# PWR_DC_DC_EXAR2.net
KiCad netlist of a schematic drawn in Altium Designer
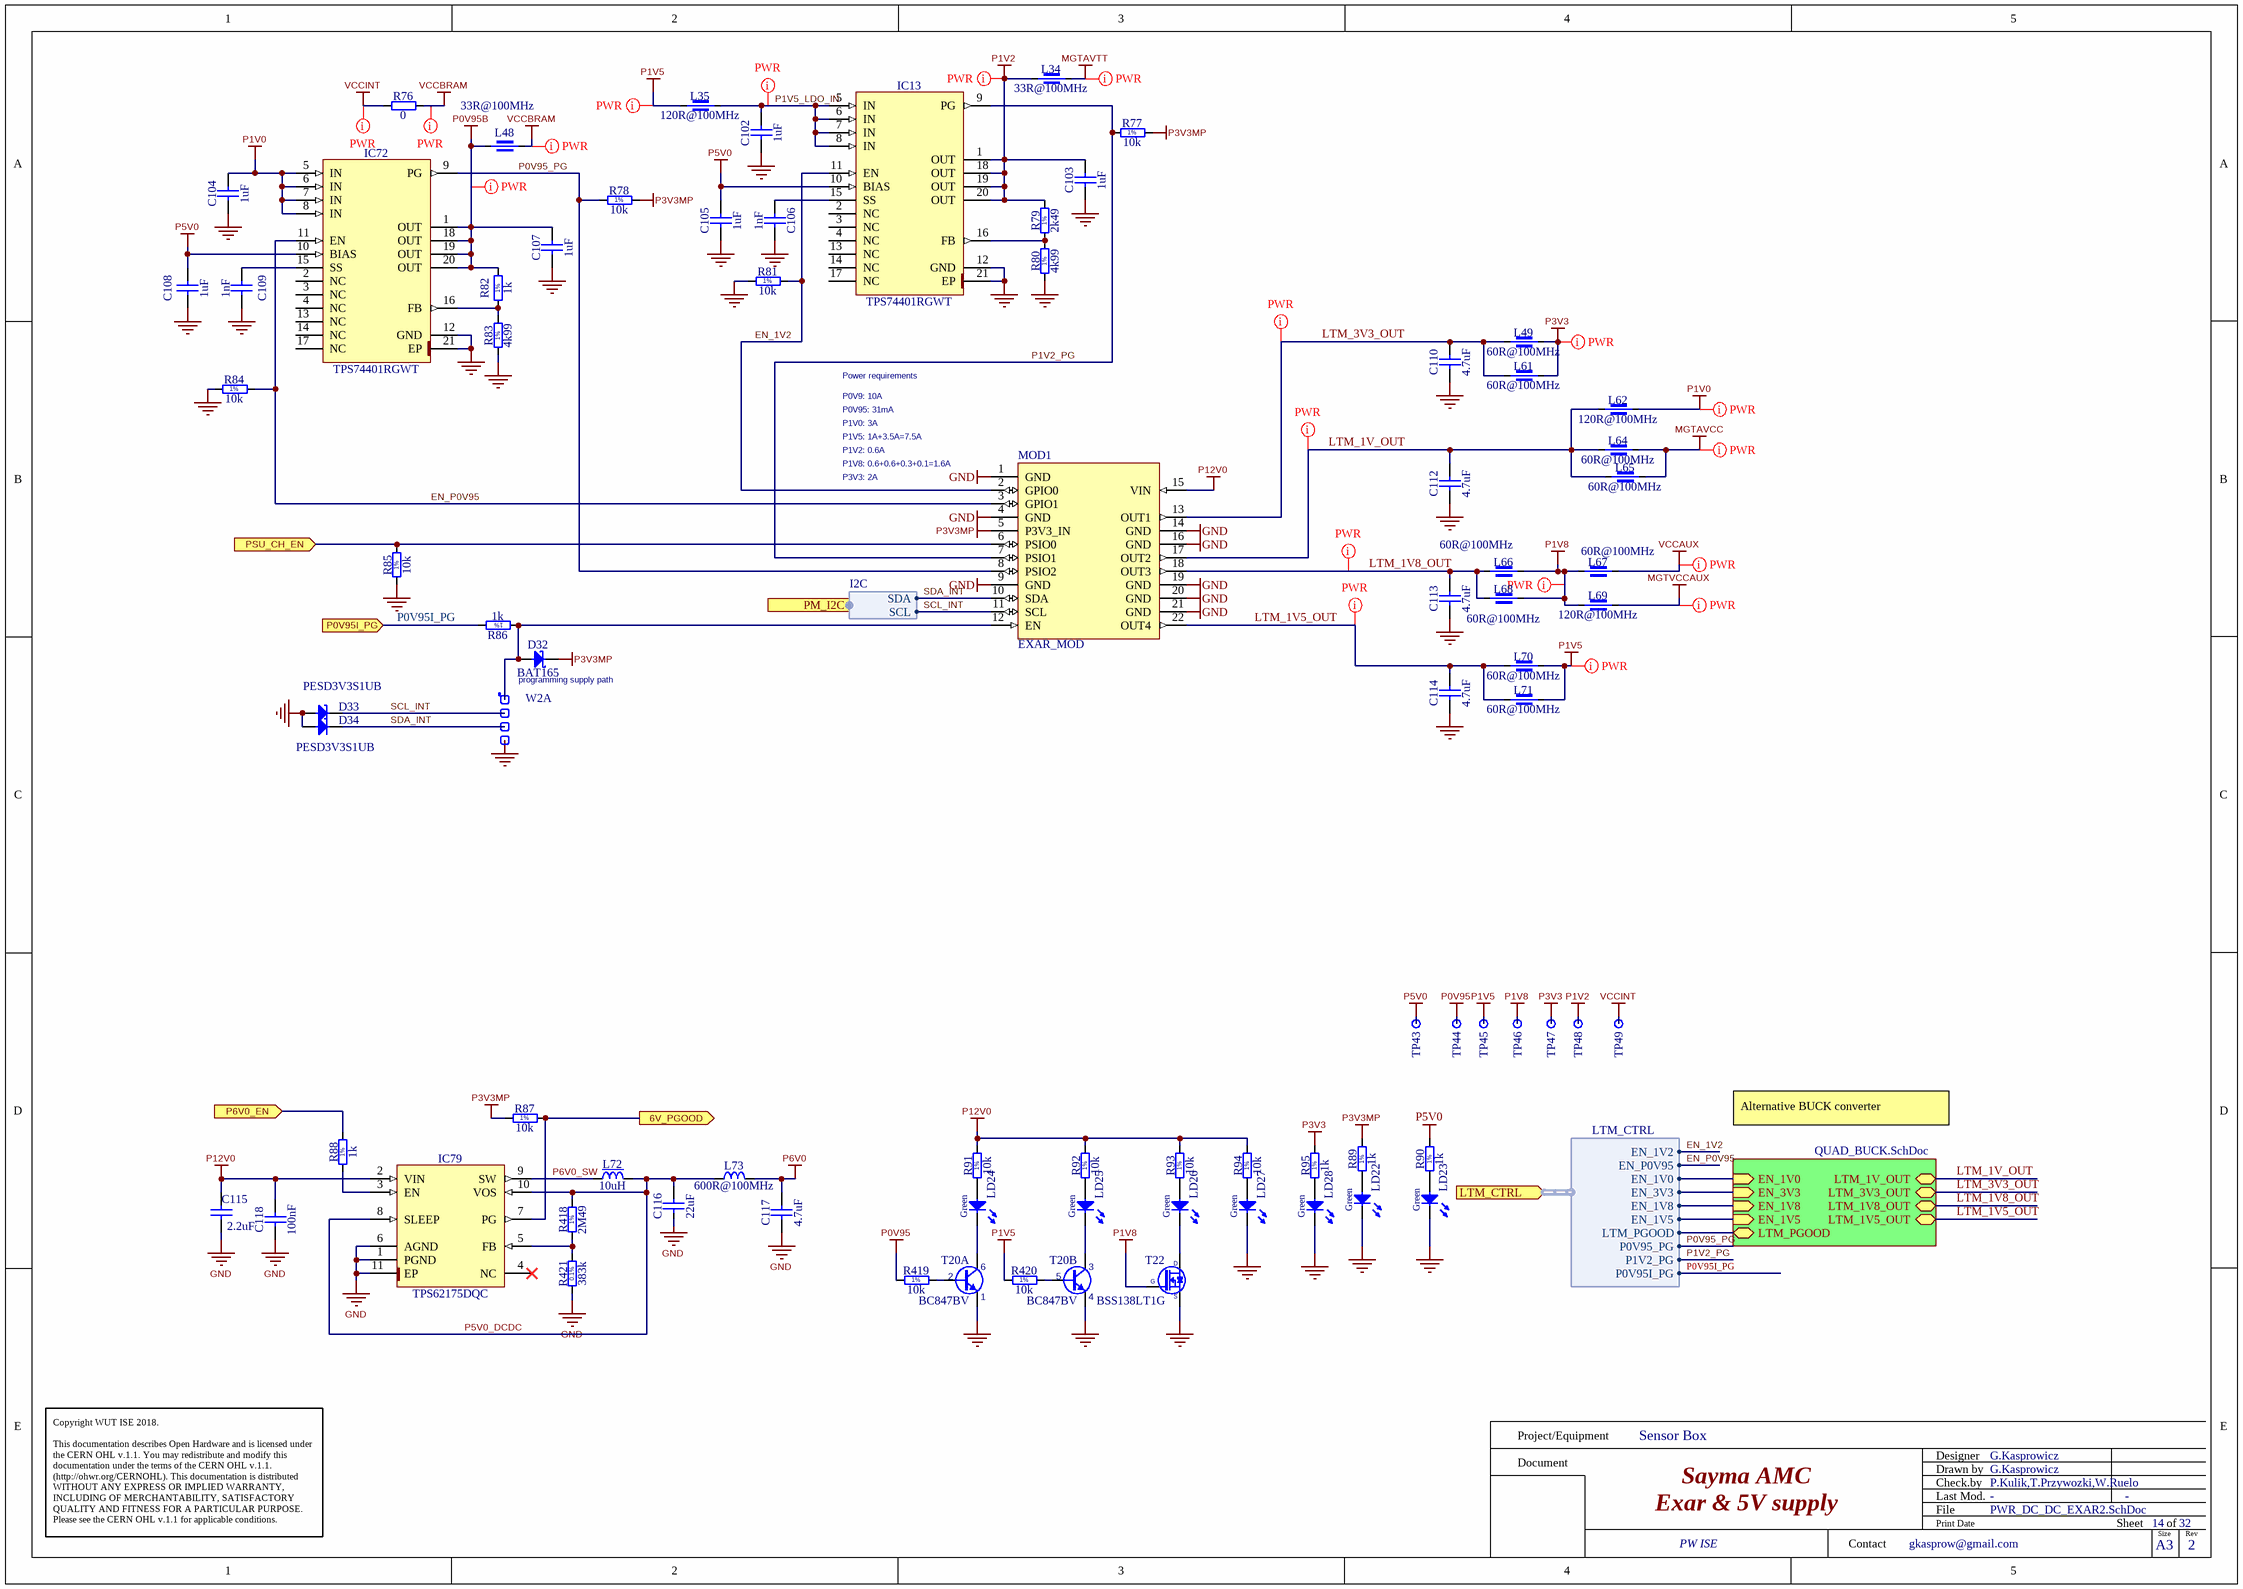
[diagram p0: PWR_DC_DC_EXAR2.SchDoc]

(export (version "E")
  (design (tool "Eeschema 10.0.6"))
  (components
    (comp (ref "C102")
      (value "1uF")
      (footprint "CAPC1005X55N")
      (description "Non-polarised capacitor")
      (fields
        (field (name "MANUFACTURER PART NUMBER") "CC0402_1UF_16V_10%_X5R")
        (field (name "MANUFACTURER") "GENERIC")
        (field (name "AUTHOR") "CERN DEM JLC")
      )
      (libsource (lib "Capacitors") (part "Capacitor - non polarized"))
    )
    (comp (ref "C103")
      (value "1uF")
      (footprint "CAPC1005X55N")
      (description "Non-polarised capacitor")
      (fields
        (field (name "MANUFACTURER PART NUMBER") "CC0402_1UF_16V_10%_X5R")
        (field (name "MANUFACTURER") "GENERIC")
        (field (name "AUTHOR") "CERN DEM JLC")
      )
      (libsource (lib "Capacitors") (part "Capacitor - non polarized"))
    )
    (comp (ref "C104")
      (value "1uF")
      (footprint "CAPC1005X55N")
      (description "Non-polarised capacitor")
      (fields
        (field (name "MANUFACTURER PART NUMBER") "CC0402_1UF_16V_10%_X5R")
        (field (name "MANUFACTURER") "GENERIC")
        (field (name "AUTHOR") "CERN DEM JLC")
      )
      (libsource (lib "Capacitors") (part "Capacitor - non polarized"))
    )
    (comp (ref "C105")
      (value "1uF")
      (footprint "CAPC1005X55N")
      (description "Non-polarised capacitor")
      (fields
        (field (name "MANUFACTURER PART NUMBER") "CC0402_1UF_16V_10%_X5R")
        (field (name "MANUFACTURER") "GENERIC")
        (field (name "AUTHOR") "CERN DEM JLC")
      )
      (libsource (lib "Capacitors") (part "Capacitor - non polarized"))
    )
    (comp (ref "C106")
      (value "1nF")
      (footprint "CAPC1005X55N")
      (description "Non-polarised capacitor")
      (fields
        (field (name "MANUFACTURER PART NUMBER") "CC0402_1NF_50V_10%_X7R")
        (field (name "MANUFACTURER") "GENERIC")
        (field (name "AUTHOR") "CERN DEM JLC")
      )
      (libsource (lib "Capacitors") (part "Capacitor - non polarized"))
    )
    (comp (ref "C107")
      (value "1uF")
      (footprint "CAPC1005X55N")
      (description "Non-polarised capacitor")
      (fields
        (field (name "MANUFACTURER PART NUMBER") "CC0402_1UF_16V_10%_X5R")
        (field (name "MANUFACTURER") "GENERIC")
        (field (name "AUTHOR") "CERN DEM JLC")
      )
      (libsource (lib "Capacitors") (part "Capacitor - non polarized"))
    )
    (comp (ref "C108")
      (value "1uF")
      (footprint "CAPC1005X55N")
      (description "Non-polarised capacitor")
      (fields
        (field (name "MANUFACTURER PART NUMBER") "CC0402_1UF_16V_10%_X5R")
        (field (name "MANUFACTURER") "GENERIC")
        (field (name "AUTHOR") "CERN DEM JLC")
      )
      (libsource (lib "Capacitors") (part "Capacitor - non polarized"))
    )
    (comp (ref "C109")
      (value "1nF")
      (footprint "CAPC1005X55N")
      (description "Non-polarised capacitor")
      (fields
        (field (name "MANUFACTURER PART NUMBER") "CC0402_1NF_50V_10%_X7R")
        (field (name "MANUFACTURER") "GENERIC")
        (field (name "AUTHOR") "CERN DEM JLC")
      )
      (libsource (lib "Capacitors") (part "Capacitor - non polarized"))
    )
    (comp (ref "C110")
      (value "4.7uF")
      (footprint "CAPC1709X95N")
      (description "Non-polarised capacitor")
      (fields
        (field (name "MANUFACTURER PART NUMBER") "CC0603_4.7UF_16V_10%_X5R")
        (field (name "MANUFACTURER") "GENERIC")
        (field (name "AUTHOR") "CERN DEM JLC")
      )
      (libsource (lib "Capacitors") (part "Capacitor - non polarized"))
    )
    (comp (ref "C112")
      (value "4.7uF")
      (footprint "CAPC1709X95N")
      (description "Non-polarised capacitor")
      (fields
        (field (name "MANUFACTURER PART NUMBER") "CC0603_4.7UF_16V_10%_X5R")
        (field (name "MANUFACTURER") "GENERIC")
        (field (name "AUTHOR") "CERN DEM JLC")
      )
      (libsource (lib "Capacitors") (part "Capacitor - non polarized"))
    )
    (comp (ref "C113")
      (value "4.7uF")
      (footprint "CAPC1709X95N")
      (description "Non-polarised capacitor")
      (fields
        (field (name "MANUFACTURER PART NUMBER") "CC0603_4.7UF_16V_10%_X5R")
        (field (name "MANUFACTURER") "GENERIC")
        (field (name "AUTHOR") "CERN DEM JLC")
      )
      (libsource (lib "Capacitors") (part "Capacitor - non polarized"))
    )
    (comp (ref "C114")
      (value "4.7uF")
      (footprint "CAPC1709X95N")
      (description "Non-polarised capacitor")
      (fields
        (field (name "MANUFACTURER PART NUMBER") "CC0603_4.7UF_16V_10%_X5R")
        (field (name "MANUFACTURER") "GENERIC")
        (field (name "AUTHOR") "CERN DEM JLC")
      )
      (libsource (lib "Capacitors") (part "Capacitor - non polarized"))
    )
    (comp (ref "C115")
      (value "2.2uF")
      (footprint "CAPC1005X55N")
      (description "Non-polarised capacitor")
      (fields
        (field (name "PART NUMBER") "CC0402_2.2UF_6.3V_10%_X5R")
        (field (name "VOLTAGE") "6.3V")
        (field (name "AUTHOR") "CERN DEM JMW")
      )
      (libsource (lib "Capacitors") (part "Capacitor - non polarized"))
    )
    (comp (ref "C116")
      (value "22uF")
      (footprint "CAPC2012X135N")
      (description "Non-polarised capacitor")
      (fields
        (field (name "MANUFACTURER PART NUMBER") "CC0805_22UF_16V_10%_X5R")
        (field (name "MANUFACTURER") "GENERIC")
        (field (name "AUTHOR") "CERN DEM JLC")
      )
      (libsource (lib "Capacitors") (part "Capacitor - non polarized"))
    )
    (comp (ref "C117")
      (value "4.7uF")
      (footprint "CAPC1709X95N")
      (description "Non-polarised capacitor")
      (fields
        (field (name "MANUFACTURER PART NUMBER") "CC0603_4.7UF_16V_10%_X5R")
        (field (name "MANUFACTURER") "GENERIC")
        (field (name "AUTHOR") "CERN DEM JLC")
      )
      (libsource (lib "Capacitors") (part "Capacitor - non polarized"))
    )
    (comp (ref "C118")
      (value "100nF")
      (footprint "CAPC1005X55N")
      (description "Non-polarised capacitor")
      (fields
        (field (name "MANUFACTURER PART NUMBER") "CC0402_100NF_16V_10%_X5R")
        (field (name "MANUFACTURER") "GENERIC")
        (field (name "AUTHOR") "CERN DEM JLC")
      )
      (libsource (lib "Capacitors") (part "Capacitor - non polarized"))
    )
    (comp (ref "D32")
      (value "BAT165")
      (footprint "SOD2512X110N")
      (description "Schottky Diode")
      (fields
        (field (name "MANUFACTURER") "INFINEON")
        (field (name "VOLTAGE") "40V")
        (field (name "AUTHOR") "CERN DEM JLC")
      )
      (libsource (lib "ICs And Semiconductors") (part "Diode Schottky"))
    )
    (comp (ref "D33")
      (value "PESD3V3S1UB")
      (footprint "SODFL1608X65N")
      (description "ESD protection diode")
      (fields
        (field (name "MANUFACTURER") "NXP SEMICONDUCTORS")
        (field (name "VOLTAGE") "3V3")
        (field (name "AUTHOR") "CERN DEM JLC")
      )
      (libsource (lib "ICs And Semiconductors") (part "Diode ESD"))
    )
    (comp (ref "D34")
      (value "PESD3V3S1UB")
      (footprint "SODFL1608X65N")
      (description "ESD protection diode")
      (fields
        (field (name "MANUFACTURER") "NXP SEMICONDUCTORS")
        (field (name "VOLTAGE") "3V3")
        (field (name "AUTHOR") "CERN DEM JLC")
      )
      (libsource (lib "ICs And Semiconductors") (part "Diode ESD"))
    )
    (comp (ref "IC13")
      (value "TPS74401RGWT")
      (footprint "QFN65P500X500X100-21N-S325")
      (description "Single Output LDO, 3.0A, Adj.(0.8 to 3.3V), Fast Transient Response, Programmable SoftStart")
      (fields (field (name "MANUFACTURER") "TEXAS INSTRUMENTS") (field (name "AUTHOR") "CERN DEM JLC"))
      (libsource (lib "ICs And Semiconductors") (part "TPS74401RGW"))
    )
    (comp (ref "IC72")
      (value "TPS74401RGWT")
      (footprint "QFN65P500X500X100-21N-S325")
      (description "Single Output LDO, 3.0A, Adj.(0.8 to 3.3V), Fast Transient Response, Programmable SoftStart")
      (fields (field (name "MANUFACTURER") "TEXAS INSTRUMENTS") (field (name "AUTHOR") "CERN DEM JLC"))
      (libsource (lib "ICs And Semiconductors") (part "TPS74401RGW"))
    )
    (comp (ref "IC79")
      (value "TPS62175DQC")
      (footprint "SON50P200X300X80-11N-R94X250")
      (description "4.75-28VDC to 1-6VDC, 500mA Step-Down Converter With Sleep Mode")
      (fields (field (name "MANUFACTURER") "TEXAS INSTRUMENTS") (field (name "AUTHOR") "CERN DEM JMW"))
      (libsource (lib "ICs And Semiconductors") (part "TPS62175"))
    )
    (comp (ref "L34")
      (value "33R@100MHz")
      (footprint "INDC1608X95N")
      (fields
        (field (name "MANUFACTURER PART NUMBER") "BLM18PG330SN1D")
        (field (name "MANUFACTURER") "MURATA")
        (field (name "PART NUMBER") "IND0603_MURATA_BLM18PG330SN1D")
        (field (name "AUTHOR") "CERN DEM JMW")
      )
      (libsource (lib "Inductors & Transformers") (part "Ferrite Bead"))
    )
    (comp (ref "L35")
      (value "120R@100MHz")
      (footprint "INDC1608X95N")
      (fields
        (field (name "MANUFACTURER PART NUMBER") "BLM18PG121SN1D")
        (field (name "MANUFACTURER") "MURATA")
        (field (name "PART NUMBER") "IND0603_MURATA_BLM18PG121SN1D")
        (field (name "AUTHOR") "CERN DEM BC")
      )
      (libsource (lib "") (part "Ferrite Bead_1"))
    )
    (comp (ref "L48")
      (value "33R@100MHz")
      (footprint "INDC1608X95N")
      (fields
        (field (name "MANUFACTURER PART NUMBER") "BLM18PG330SN1D")
        (field (name "MANUFACTURER") "MURATA")
        (field (name "PART NUMBER") "IND0603_MURATA_BLM18PG330SN1D")
        (field (name "AUTHOR") "CERN DEM JMW")
      )
      (libsource (lib "Inductors & Transformers") (part "Ferrite Bead"))
    )
    (comp (ref "L49")
      (value "60R@100MHz")
      (footprint "INDC4516X180N")
      (fields
        (field (name "MANUFACTURER PART NUMBER") "BLM41PG600SN1L")
        (field (name "MANUFACTURER") "MURATA")
        (field (name "PART NUMBER") "IND1806_MURATA_BLM41PG600SN1L")
        (field (name "AUTHOR") "CERN DEM JLC")
      )
      (libsource (lib "Inductors & Transformers") (part "Ferrite Bead"))
    )
    (comp (ref "L61")
      (value "60R@100MHz")
      (footprint "INDC4516X180N")
      (fields
        (field (name "MANUFACTURER PART NUMBER") "BLM41PG600SN1L")
        (field (name "MANUFACTURER") "MURATA")
        (field (name "PART NUMBER") "IND1806_MURATA_BLM41PG600SN1L")
        (field (name "AUTHOR") "CERN DEM JLC")
      )
      (libsource (lib "Inductors & Transformers") (part "Ferrite Bead"))
    )
    (comp (ref "L62")
      (value "120R@100MHz")
      (footprint "INDC1608X95N")
      (fields
        (field (name "MANUFACTURER PART NUMBER") "BLM18PG121SN1D")
        (field (name "MANUFACTURER") "MURATA")
        (field (name "PART NUMBER") "IND0603_MURATA_BLM18PG121SN1D")
        (field (name "AUTHOR") "CERN DEM BC")
      )
      (libsource (lib "") (part "Ferrite Bead_1"))
    )
    (comp (ref "L64")
      (value "60R@100MHz")
      (footprint "INDC4516X180N")
      (fields
        (field (name "MANUFACTURER PART NUMBER") "BLM41PG600SN1L")
        (field (name "MANUFACTURER") "MURATA")
        (field (name "PART NUMBER") "IND1806_MURATA_BLM41PG600SN1L")
        (field (name "AUTHOR") "CERN DEM JLC")
      )
      (libsource (lib "Inductors & Transformers") (part "Ferrite Bead"))
    )
    (comp (ref "L65")
      (value "60R@100MHz")
      (footprint "INDC4516X180N")
      (fields
        (field (name "MANUFACTURER PART NUMBER") "BLM41PG600SN1L")
        (field (name "MANUFACTURER") "MURATA")
        (field (name "PART NUMBER") "IND1806_MURATA_BLM41PG600SN1L")
        (field (name "AUTHOR") "CERN DEM JLC")
      )
      (libsource (lib "Inductors & Transformers") (part "Ferrite Bead"))
    )
    (comp (ref "L66")
      (value "60R@100MHz")
      (footprint "INDC4516X180N")
      (fields
        (field (name "MANUFACTURER PART NUMBER") "BLM41PG600SN1L")
        (field (name "MANUFACTURER") "MURATA")
        (field (name "PART NUMBER") "IND1806_MURATA_BLM41PG600SN1L")
        (field (name "AUTHOR") "CERN DEM JLC")
      )
      (libsource (lib "Inductors & Transformers") (part "Ferrite Bead"))
    )
    (comp (ref "L67")
      (value "60R@100MHz")
      (footprint "INDC4516X180N")
      (fields
        (field (name "MANUFACTURER PART NUMBER") "BLM41PG600SN1L")
        (field (name "MANUFACTURER") "MURATA")
        (field (name "PART NUMBER") "IND1806_MURATA_BLM41PG600SN1L")
        (field (name "AUTHOR") "CERN DEM JLC")
      )
      (libsource (lib "Inductors & Transformers") (part "Ferrite Bead"))
    )
    (comp (ref "L68")
      (value "60R@100MHz")
      (footprint "INDC4516X180N")
      (fields
        (field (name "MANUFACTURER PART NUMBER") "BLM41PG600SN1L")
        (field (name "MANUFACTURER") "MURATA")
        (field (name "PART NUMBER") "IND1806_MURATA_BLM41PG600SN1L")
        (field (name "AUTHOR") "CERN DEM JLC")
      )
      (libsource (lib "Inductors & Transformers") (part "Ferrite Bead"))
    )
    (comp (ref "L69")
      (value "120R@100MHz")
      (footprint "INDC1608X95N")
      (fields
        (field (name "MANUFACTURER PART NUMBER") "BLM18PG121SN1D")
        (field (name "MANUFACTURER") "MURATA")
        (field (name "PART NUMBER") "IND0603_MURATA_BLM18PG121SN1D")
        (field (name "AUTHOR") "CERN DEM BC")
      )
      (libsource (lib "") (part "Ferrite Bead_1"))
    )
    (comp (ref "L70")
      (value "60R@100MHz")
      (footprint "INDC4516X180N")
      (fields
        (field (name "MANUFACTURER PART NUMBER") "BLM41PG600SN1L")
        (field (name "MANUFACTURER") "MURATA")
        (field (name "PART NUMBER") "IND1806_MURATA_BLM41PG600SN1L")
        (field (name "AUTHOR") "CERN DEM JLC")
      )
      (libsource (lib "Inductors & Transformers") (part "Ferrite Bead"))
    )
    (comp (ref "L71")
      (value "60R@100MHz")
      (footprint "INDC4516X180N")
      (fields
        (field (name "MANUFACTURER PART NUMBER") "BLM41PG600SN1L")
        (field (name "MANUFACTURER") "MURATA")
        (field (name "PART NUMBER") "IND1806_MURATA_BLM41PG600SN1L")
        (field (name "AUTHOR") "CERN DEM JLC")
      )
      (libsource (lib "Inductors & Transformers") (part "Ferrite Bead"))
    )
    (comp (ref "L72")
      (value "10uH")
      (footprint "IND_WURTH_WE-SPC-4838")
      (description "Inductor With Core")
      (fields
        (field (name "PART NUMBER") "IND_10UH_20%_WURTH_WE-SPC_74408943100")
        (field (name "POWER") "1.65A")
        (field (name "AUTHOR") "CERN DEM MR")
      )
      (libsource (lib "Inductors & Transformers") (part "Inductor With Magnetic core"))
    )
    (comp (ref "L73")
      (value "600R@100MHz")
      (footprint "INDC2012X110N")
      (description "Inductor")
      (fields
        (field (name "MANUFACTURER PART NUMBER") "742792040")
        (field (name "MANUFACTURER") "WURTH ELEKTRONIK")
        (field (name "AUTHOR") "CERN DEM JLC")
      )
      (libsource (lib "Inductors & Transformers") (part "Inductor"))
    )
    (comp (ref "LD22")
      (value "Green")
      (footprint "LED_KINGBRIGHT_KPH-1608CGCK")
      (description "LED Green 1C 2A")
      (fields
        (field (name "MANUFACTURER PART NUMBER") "KPH-1608CGCK")
        (field (name "MANUFACTURER") "KINGBRIGHT")
        (field (name "AUTHOR") "CERN DEM JLC")
      )
      (libsource (lib "ICs And Semiconductors") (part "LED Green 1C 2A"))
    )
    (comp (ref "LD23")
      (value "Green")
      (footprint "LED_KINGBRIGHT_KPH-1608CGCK")
      (description "LED Green 1C 2A")
      (fields
        (field (name "MANUFACTURER PART NUMBER") "KPH-1608CGCK")
        (field (name "MANUFACTURER") "KINGBRIGHT")
        (field (name "AUTHOR") "CERN DEM JLC")
      )
      (libsource (lib "ICs And Semiconductors") (part "LED Green 1C 2A"))
    )
    (comp (ref "LD24")
      (value "Green")
      (footprint "LED_KINGBRIGHT_KPH-1608CGCK")
      (description "LED Green 1C 2A")
      (fields
        (field (name "MANUFACTURER PART NUMBER") "KPH-1608CGCK")
        (field (name "MANUFACTURER") "KINGBRIGHT")
        (field (name "AUTHOR") "CERN DEM JLC")
      )
      (libsource (lib "ICs And Semiconductors") (part "LED Green 1C 2A"))
    )
    (comp (ref "LD25")
      (value "Green")
      (footprint "LED_KINGBRIGHT_KPH-1608CGCK")
      (description "LED Green 1C 2A")
      (fields
        (field (name "MANUFACTURER PART NUMBER") "KPH-1608CGCK")
        (field (name "MANUFACTURER") "KINGBRIGHT")
        (field (name "AUTHOR") "CERN DEM JLC")
      )
      (libsource (lib "ICs And Semiconductors") (part "LED Green 1C 2A"))
    )
    (comp (ref "LD26")
      (value "Green")
      (footprint "LED_KINGBRIGHT_KPH-1608CGCK")
      (description "LED Green 1C 2A")
      (fields
        (field (name "MANUFACTURER PART NUMBER") "KPH-1608CGCK")
        (field (name "MANUFACTURER") "KINGBRIGHT")
        (field (name "AUTHOR") "CERN DEM JLC")
      )
      (libsource (lib "ICs And Semiconductors") (part "LED Green 1C 2A"))
    )
    (comp (ref "LD27")
      (value "Green")
      (footprint "LED_KINGBRIGHT_KPH-1608CGCK")
      (description "LED Green 1C 2A")
      (fields
        (field (name "MANUFACTURER PART NUMBER") "KPH-1608CGCK")
        (field (name "MANUFACTURER") "KINGBRIGHT")
        (field (name "AUTHOR") "CERN DEM JLC")
      )
      (libsource (lib "ICs And Semiconductors") (part "LED Green 1C 2A"))
    )
    (comp (ref "LD28")
      (value "Green")
      (footprint "LED_KINGBRIGHT_KPH-1608CGCK")
      (description "LED Green 1C 2A")
      (fields
        (field (name "MANUFACTURER PART NUMBER") "KPH-1608CGCK")
        (field (name "MANUFACTURER") "KINGBRIGHT")
        (field (name "AUTHOR") "CERN DEM JLC")
      )
      (libsource (lib "ICs And Semiconductors") (part "LED Green 1C 2A"))
    )
    (comp (ref "MOD1")
      (value "EXAR_MOD")
      (footprint "EXAR_MOD")
      (description "4 channel PCB module based on XRP7724ILB-F")
      (libsource (lib "LIBRARY_SCH") (part "DC/DC_EXAR_MOD"))
    )
    (comp (ref "R76")
      (value "0")
      (footprint "RESC2012X60N")
      (description "Resistor")
      (fields
        (field (name "PART NUMBER") "R0805_0R_JUMPER")
        (field (name "MANUFACTURER") "GENERIC")
        (field (name "AUTHOR") "CERN DEM JLC")
      )
      (libsource (lib "Resistors") (part "Resistor"))
    )
    (comp (ref "R77")
      (value "10k")
      (footprint "RESC1005X40N")
      (description "Resistor - 1%")
      (fields
        (field (name "MANUFACTURER PART NUMBER") "R0402_10K_1%_0.0625W_100PPM")
        (field (name "MANUFACTURER") "GENERIC")
        (field (name "AUTHOR") "CERN DEM JLC")
      )
      (libsource (lib "Resistors") (part "Resistor - 1%"))
    )
    (comp (ref "R78")
      (value "10k")
      (footprint "RESC1005X40N")
      (description "Resistor - 1%")
      (fields
        (field (name "MANUFACTURER PART NUMBER") "R0402_10K_1%_0.0625W_100PPM")
        (field (name "MANUFACTURER") "GENERIC")
        (field (name "AUTHOR") "CERN DEM JLC")
      )
      (libsource (lib "Resistors") (part "Resistor - 1%"))
    )
    (comp (ref "R79")
      (value "2k49")
      (footprint "RESC1608X55N")
      (description "Resistor - 1%")
      (fields
        (field (name "MANUFACTURER PART NUMBER") "R0603_2K49_1%_0.063W_50PPM")
        (field (name "MANUFACTURER") "GENERIC")
        (field (name "AUTHOR") "CERN DEM JLC")
      )
      (libsource (lib "Resistors") (part "Resistor - 1%"))
    )
    (comp (ref "R80")
      (value "4k99")
      (footprint "RESC1608X55N")
      (description "Resistor - 1%")
      (fields
        (field (name "MANUFACTURER PART NUMBER") "R0603_4K99_1%_0.063W_50PPM")
        (field (name "MANUFACTURER") "GENERIC")
        (field (name "AUTHOR") "CERN DEM JLC")
      )
      (libsource (lib "Resistors") (part "Resistor - 1%"))
    )
    (comp (ref "R81")
      (value "10k")
      (footprint "RESC1005X40N")
      (description "Resistor - 1%")
      (fields
        (field (name "MANUFACTURER PART NUMBER") "R0402_10K_1%_0.0625W_100PPM")
        (field (name "MANUFACTURER") "GENERIC")
        (field (name "AUTHOR") "CERN DEM JLC")
      )
      (libsource (lib "Resistors") (part "Resistor - 1%"))
    )
    (comp (ref "R82")
      (value "1k")
      (footprint "RESC1005X40N")
      (description "Resistor - 1%")
      (fields
        (field (name "MANUFACTURER PART NUMBER") "R0402_1K_1%_0.0625W_100PPM")
        (field (name "MANUFACTURER") "GENERIC")
        (field (name "AUTHOR") "CERN DEM JLC")
      )
      (libsource (lib "Resistors") (part "Resistor - 1%"))
    )
    (comp (ref "R83")
      (value "4k99")
      (footprint "RESC1608X55N")
      (description "Resistor - 1%")
      (fields
        (field (name "MANUFACTURER PART NUMBER") "R0603_4K99_1%_0.063W_50PPM")
        (field (name "MANUFACTURER") "GENERIC")
        (field (name "AUTHOR") "CERN DEM JLC")
      )
      (libsource (lib "Resistors") (part "Resistor - 1%"))
    )
    (comp (ref "R84")
      (value "10k")
      (footprint "RESC1005X40N")
      (description "Resistor - 1%")
      (fields
        (field (name "MANUFACTURER PART NUMBER") "R0402_10K_1%_0.0625W_100PPM")
        (field (name "MANUFACTURER") "GENERIC")
        (field (name "AUTHOR") "CERN DEM JLC")
      )
      (libsource (lib "Resistors") (part "Resistor - 1%"))
    )
    (comp (ref "R85")
      (value "10k")
      (footprint "RESC1005X40N")
      (description "Resistor - 1%")
      (fields
        (field (name "MANUFACTURER PART NUMBER") "R0402_10K_1%_0.0625W_100PPM")
        (field (name "MANUFACTURER") "GENERIC")
        (field (name "AUTHOR") "CERN DEM JLC")
      )
      (libsource (lib "Resistors") (part "Resistor - 1%"))
    )
    (comp (ref "R86")
      (value "1k")
      (footprint "RESC1005X40N")
      (description "Resistor - 1%")
      (fields
        (field (name "MANUFACTURER PART NUMBER") "R0402_1K_1%_0.0625W_100PPM")
        (field (name "MANUFACTURER") "GENERIC")
        (field (name "AUTHOR") "CERN DEM JLC")
      )
      (libsource (lib "Resistors") (part "Resistor - 1%"))
    )
    (comp (ref "R87")
      (value "10k")
      (footprint "RESC1005X40N")
      (description "Resistor - 1%")
      (fields
        (field (name "MANUFACTURER PART NUMBER") "R0402_10K_1%_0.0625W_100PPM")
        (field (name "MANUFACTURER") "GENERIC")
        (field (name "AUTHOR") "CERN DEM JLC")
      )
      (libsource (lib "Resistors") (part "Resistor - 1%"))
    )
    (comp (ref "R88")
      (value "1k")
      (footprint "RESC1005X40N")
      (description "Resistor - 1%")
      (fields
        (field (name "MANUFACTURER PART NUMBER") "R0402_1K_1%_0.0625W_100PPM")
        (field (name "MANUFACTURER") "GENERIC")
        (field (name "AUTHOR") "CERN DEM JLC")
      )
      (libsource (lib "Resistors") (part "Resistor - 1%"))
    )
    (comp (ref "R89")
      (value "1k")
      (footprint "RESC1005X40N")
      (description "Resistor - 1%")
      (fields
        (field (name "MANUFACTURER PART NUMBER") "R0402_1K_1%_0.0625W_100PPM")
        (field (name "MANUFACTURER") "GENERIC")
        (field (name "AUTHOR") "CERN DEM JLC")
      )
      (libsource (lib "Resistors") (part "Resistor - 1%"))
    )
    (comp (ref "R90")
      (value "1k")
      (footprint "RESC1005X40N")
      (description "Resistor - 1%")
      (fields
        (field (name "MANUFACTURER PART NUMBER") "R0402_1K_1%_0.0625W_100PPM")
        (field (name "MANUFACTURER") "GENERIC")
        (field (name "AUTHOR") "CERN DEM JLC")
      )
      (libsource (lib "Resistors") (part "Resistor - 1%"))
    )
    (comp (ref "R91")
      (value "10k")
      (footprint "RESC1005X40N")
      (description "Resistor - 1%")
      (fields
        (field (name "MANUFACTURER PART NUMBER") "R0402_10K_1%_0.0625W_100PPM")
        (field (name "MANUFACTURER") "GENERIC")
        (field (name "AUTHOR") "CERN DEM JLC")
      )
      (libsource (lib "Resistors") (part "Resistor - 1%"))
    )
    (comp (ref "R92")
      (value "10k")
      (footprint "RESC1005X40N")
      (description "Resistor - 1%")
      (fields
        (field (name "MANUFACTURER PART NUMBER") "R0402_10K_1%_0.0625W_100PPM")
        (field (name "MANUFACTURER") "GENERIC")
        (field (name "AUTHOR") "CERN DEM JLC")
      )
      (libsource (lib "Resistors") (part "Resistor - 1%"))
    )
    (comp (ref "R93")
      (value "10k")
      (footprint "RESC1005X40N")
      (description "Resistor - 1%")
      (fields
        (field (name "MANUFACTURER PART NUMBER") "R0402_10K_1%_0.0625W_100PPM")
        (field (name "MANUFACTURER") "GENERIC")
        (field (name "AUTHOR") "CERN DEM JLC")
      )
      (libsource (lib "Resistors") (part "Resistor - 1%"))
    )
    (comp (ref "R94")
      (value "10k")
      (footprint "RESC1005X40N")
      (description "Resistor - 1%")
      (fields
        (field (name "MANUFACTURER PART NUMBER") "R0402_10K_1%_0.0625W_100PPM")
        (field (name "MANUFACTURER") "GENERIC")
        (field (name "AUTHOR") "CERN DEM JLC")
      )
      (libsource (lib "Resistors") (part "Resistor - 1%"))
    )
    (comp (ref "R95")
      (value "1k")
      (footprint "RESC1005X40N")
      (description "Resistor - 1%")
      (fields
        (field (name "MANUFACTURER PART NUMBER") "R0402_1K_1%_0.0625W_100PPM")
        (field (name "MANUFACTURER") "GENERIC")
        (field (name "AUTHOR") "CERN DEM JLC")
      )
      (libsource (lib "Resistors") (part "Resistor - 1%"))
    )
    (comp (ref "R418")
      (value "2M49")
      (footprint "RESC1608X55N")
      (description "Resistor - 1%")
      (fields
        (field (name "PART NUMBER") "R0603_2M49_1%_0.1W_100PPM")
        (field (name "POWER") "0.1W")
        (field (name "AUTHOR") "CERN DEM JLC")
      )
      (libsource (lib "Resistors") (part "Resistor - 1%"))
    )
    (comp (ref "R419")
      (value "10k")
      (footprint "RESC1005X40N")
      (description "Resistor - 1%")
      (fields
        (field (name "MANUFACTURER PART NUMBER") "R0402_10K_1%_0.0625W_100PPM")
        (field (name "MANUFACTURER") "GENERIC")
        (field (name "AUTHOR") "CERN DEM JLC")
      )
      (libsource (lib "Resistors") (part "Resistor - 1%"))
    )
    (comp (ref "R420")
      (value "10k")
      (footprint "RESC1005X40N")
      (description "Resistor - 1%")
      (fields
        (field (name "MANUFACTURER PART NUMBER") "R0402_10K_1%_0.0625W_100PPM")
        (field (name "MANUFACTURER") "GENERIC")
        (field (name "AUTHOR") "CERN DEM JLC")
      )
      (libsource (lib "Resistors") (part "Resistor - 1%"))
    )
    (comp (ref "R421")
      (value "383k")
      (footprint "RESC1608X55N")
      (description "Resistor - 0.1%")
      (fields
        (field (name "PART NUMBER") "R0603_383K_0.1%_0.063W_25PPM")
        (field (name "POWER") "0.063W")
        (field (name "AUTHOR") "CERN DEM JLC")
      )
      (libsource (lib "Resistors") (part "Resistor - 0.1%"))
    )
    (comp (ref "T20")
      (value "BC847BV")
      (footprint "SOTFL50P160X60-6N")
      (description "45V, 100mA NPN General Purpose Double Transistor")
      (fields (field (name "MANUFACTURER") "NXP SEMICONDUCTORS") (field (name "AUTHOR") "CERN DEM JLC"))
      (libsource (lib "ICs And Semiconductors") (part "BC847BV"))
    )
    (comp (ref "T22")
      (value "BSS138LT1G")
      (footprint "SOT95P240X110-3N")
      (description "N-CHANNEL MOSFET WITH DIODE")
      (fields (field (name "MANUFACTURER") "ON SEMICONDUCTOR") (field (name "AUTHOR") "CERN DEM JLC"))
      (libsource (lib "ICs And Semiconductors") (part "N-MOSFET-D 1G 2S 3D"))
    )
    (comp (ref "TP43")
      (value "Test Point")
      (footprint "TPS127")
      (fields (field (name "PART NUMBER") "SMD_PAD_1.27X1.27MM") (field (name "AUTHOR") "CERN DEM JLC"))
      (libsource (lib "Eletro-mechanical") (part "Test Point"))
    )
    (comp (ref "TP44")
      (value "Test Point")
      (footprint "TPS127")
      (fields (field (name "PART NUMBER") "SMD_PAD_1.27X1.27MM") (field (name "AUTHOR") "CERN DEM JLC"))
      (libsource (lib "Eletro-mechanical") (part "Test Point"))
    )
    (comp (ref "TP45")
      (value "Test Point")
      (footprint "TPS127")
      (fields (field (name "PART NUMBER") "SMD_PAD_1.27X1.27MM") (field (name "AUTHOR") "CERN DEM JLC"))
      (libsource (lib "Eletro-mechanical") (part "Test Point"))
    )
    (comp (ref "TP46")
      (value "Test Point")
      (footprint "TPS127")
      (fields (field (name "PART NUMBER") "SMD_PAD_1.27X1.27MM") (field (name "AUTHOR") "CERN DEM JLC"))
      (libsource (lib "Eletro-mechanical") (part "Test Point"))
    )
    (comp (ref "TP47")
      (value "Test Point")
      (footprint "TPS127")
      (fields (field (name "PART NUMBER") "SMD_PAD_1.27X1.27MM") (field (name "AUTHOR") "CERN DEM JLC"))
      (libsource (lib "Eletro-mechanical") (part "Test Point"))
    )
    (comp (ref "TP48")
      (value "Test Point")
      (footprint "TPS127")
      (fields (field (name "PART NUMBER") "SMD_PAD_1.27X1.27MM") (field (name "AUTHOR") "CERN DEM JLC"))
      (libsource (lib "Eletro-mechanical") (part "Test Point"))
    )
    (comp (ref "TP49")
      (value "Test Point")
      (footprint "TPS127")
      (fields (field (name "PART NUMBER") "SMD_PAD_1.27X1.27MM") (field (name "AUTHOR") "CERN DEM JLC"))
      (libsource (lib "Eletro-mechanical") (part "Test Point"))
    )
    (comp (ref "W2")
      (value "Header 4")
      (footprint "SAMTEC_MTLW-104-07-L-S-250")
      (description "4 Mini Wire-Wrap Contact Strip Header")
      (fields
        (field (name "MANUFACTURER PART NUMBER") "MTLW-104-07-L-S-250")
        (field (name "MANUFACTURER") "SAMTEC")
        (field (name "AUTHOR") "CERN DEM JLC")
      )
      (libsource (lib "Connectors") (part "Wire-Wrap Contact x4"))
    )
    (comp (ref "W11")
      (value "Header 4")
      (footprint "SAMTEC_MTLW-104-07-L-S-250")
      (description "4 Mini Wire-Wrap Contact Strip Header")
      (fields
        (field (name "MANUFACTURER PART NUMBER") "MTLW-104-07-L-S-250")
        (field (name "MANUFACTURER") "SAMTEC")
        (field (name "AUTHOR") "CERN DEM JLC")
      )
      (libsource (lib "Connectors") (part "Wire-Wrap Contact x4"))
    )
  )
  (nets
    (net (code "3") (name "/6V_PGOOD") (class "Default")
      (node (ref "IC79") (pin "7") (pinfunction "PG_7") (pintype "output"))
      (node (ref "R87") (pin "2") (pinfunction "2_2") (pintype "passive"))
    )
    (net (code "5") (name "/EN_1V2") (class "Default")
      (node (ref "IC13") (pin "11") (pinfunction "EN_11") (pintype "input"))
      (node (ref "MOD1") (pin "2") (pinfunction "GPIO0_2") (pintype "bidirectional"))
      (node (ref "R81") (pin "2") (pinfunction "2_2") (pintype "passive"))
    )
    (net (code "9") (name "/EN_P0V95") (class "Default")
      (node (ref "IC72") (pin "11") (pinfunction "EN_11") (pintype "input"))
      (node (ref "MOD1") (pin "3") (pinfunction "GPIO1_3") (pintype "bidirectional"))
      (node (ref "R84") (pin "2") (pinfunction "2_2") (pintype "passive"))
    )
    (net (code "10") (name "/LTM_1V5_OUT") (class "Default")
      (node (ref "C114") (pin "2") (pinfunction "2_2") (pintype "passive"))
      (node (ref "L70") (pin "1") (pinfunction "1_1") (pintype "passive"))
      (node (ref "L71") (pin "1") (pinfunction "1_1") (pintype "passive"))
      (node (ref "MOD1") (pin "22") (pinfunction "OUT4_22") (pintype "output"))
    )
    (net (code "11") (name "/LTM_1V8_OUT") (class "Default")
      (node (ref "C113") (pin "2") (pinfunction "2_2") (pintype "passive"))
      (node (ref "L66") (pin "1") (pinfunction "1_1") (pintype "passive"))
      (node (ref "L68") (pin "1") (pinfunction "1_1") (pintype "passive"))
      (node (ref "MOD1") (pin "18") (pinfunction "OUT3_18") (pintype "output"))
    )
    (net (code "12") (name "/LTM_1V_OUT") (class "Default")
      (node (ref "C112") (pin "2") (pinfunction "2_2") (pintype "passive"))
      (node (ref "L62") (pin "2") (pinfunction "2_2") (pintype "passive"))
      (node (ref "L64") (pin "1") (pinfunction "1_1") (pintype "passive"))
      (node (ref "L65") (pin "1") (pinfunction "1_1") (pintype "passive"))
      (node (ref "MOD1") (pin "17") (pinfunction "OUT2_17") (pintype "output"))
    )
    (net (code "13") (name "/LTM_3V3_OUT") (class "Default")
      (node (ref "C110") (pin "2") (pinfunction "2_2") (pintype "passive"))
      (node (ref "L49") (pin "1") (pinfunction "1_1") (pintype "passive"))
      (node (ref "L61") (pin "1") (pinfunction "1_1") (pintype "passive"))
      (node (ref "MOD1") (pin "13") (pinfunction "OUT1_13") (pintype "output"))
    )
    (net (code "15") (name "/P0V95I_PG") (class "Default")
      (node (ref "R86") (pin "2") (pinfunction "2_2") (pintype "passive"))
    )
    (net (code "16") (name "/P0V95_PG") (class "Default")
      (node (ref "IC72") (pin "9") (pinfunction "PG_9") (pintype "output"))
      (node (ref "MOD1") (pin "8") (pinfunction "PSIO2_8") (pintype "bidirectional"))
      (node (ref "R78") (pin "1") (pinfunction "1_1") (pintype "passive"))
    )
    (net (code "17") (name "/P1V2_PG") (class "Default")
      (node (ref "IC13") (pin "9") (pinfunction "PG_9") (pintype "output"))
      (node (ref "MOD1") (pin "7") (pinfunction "PSIO1_7") (pintype "bidirectional"))
      (node (ref "R77") (pin "1") (pinfunction "1_1") (pintype "passive"))
    )
    (net (code "18") (name "/P1V5_LDO_IN") (class "Default")
      (node (ref "C102") (pin "2") (pinfunction "2_2") (pintype "passive"))
      (node (ref "IC13") (pin "5") (pinfunction "IN_5") (pintype "input"))
      (node (ref "IC13") (pin "6") (pinfunction "IN_6") (pintype "input"))
      (node (ref "IC13") (pin "7") (pinfunction "IN_7") (pintype "input"))
      (node (ref "IC13") (pin "8") (pinfunction "IN_8") (pintype "input"))
      (node (ref "L35") (pin "1") (pinfunction "1_1") (pintype "passive"))
    )
    (net (code "19") (name "/P5V0_DCDC") (class "Default")
      (node (ref "C116") (pin "2") (pinfunction "2_2") (pintype "passive"))
      (node (ref "IC79") (pin "10") (pinfunction "VOS_10") (pintype "input"))
      (node (ref "IC79") (pin "8") (pinfunction "SLEEP_8") (pintype "input"))
      (node (ref "L72") (pin "2") (pinfunction "2_2") (pintype "passive"))
      (node (ref "L73") (pin "1") (pinfunction "1_1") (pintype "passive"))
      (node (ref "R418") (pin "2") (pinfunction "2_2") (pintype "passive"))
    )
    (net (code "20") (name "/P6V0_EN") (class "Default")
      (node (ref "R88") (pin "2") (pinfunction "2_2") (pintype "passive"))
    )
    (net (code "21") (name "/P6V0_SW") (class "Default")
      (node (ref "IC79") (pin "9") (pinfunction "SW_9") (pintype "output"))
      (node (ref "L72") (pin "1") (pinfunction "1_1") (pintype "passive"))
    )
    (net (code "22") (name "/PSU_CH_EN") (class "Default")
      (node (ref "MOD1") (pin "6") (pinfunction "PSIO0_6") (pintype "bidirectional"))
      (node (ref "R85") (pin "2") (pinfunction "2_2") (pintype "passive"))
    )
    (net (code "23") (name "/SCL_INT") (class "Default")
      (node (ref "D33") (pin "1") (pinfunction "C_1") (pintype "passive"))
      (node (ref "MOD1") (pin "11") (pinfunction "SCL_11") (pintype "bidirectional"))
      (node (ref "W11") (pin "2") (pinfunction "2_2") (pintype "bidirectional"))
    )
    (net (code "24") (name "/SDA_INT") (class "Default")
      (node (ref "D34") (pin "1") (pinfunction "C_1") (pintype "passive"))
      (node (ref "MOD1") (pin "10") (pinfunction "SDA_10") (pintype "bidirectional"))
      (node (ref "W11") (pin "3") (pinfunction "3_3") (pintype "bidirectional"))
    )
    (net (code "27") (name "GND") (class "Default")
      (node (ref "C102") (pin "1") (pinfunction "1_1") (pintype "passive"))
      (node (ref "C103") (pin "1") (pinfunction "1_1") (pintype "passive"))
      (node (ref "C104") (pin "1") (pinfunction "1_1") (pintype "passive"))
      (node (ref "C105") (pin "1") (pinfunction "1_1") (pintype "passive"))
      (node (ref "C106") (pin "2") (pinfunction "2_2") (pintype "passive"))
      (node (ref "C107") (pin "1") (pinfunction "1_1") (pintype "passive"))
      (node (ref "C108") (pin "1") (pinfunction "1_1") (pintype "passive"))
      (node (ref "C109") (pin "2") (pinfunction "2_2") (pintype "passive"))
      (node (ref "C110") (pin "1") (pinfunction "1_1") (pintype "passive"))
      (node (ref "C112") (pin "1") (pinfunction "1_1") (pintype "passive"))
      (node (ref "C113") (pin "1") (pinfunction "1_1") (pintype "passive"))
      (node (ref "C114") (pin "1") (pinfunction "1_1") (pintype "passive"))
      (node (ref "C115") (pin "1") (pinfunction "1_1") (pintype "passive"))
      (node (ref "C116") (pin "1") (pinfunction "1_1") (pintype "passive"))
      (node (ref "C117") (pin "1") (pinfunction "1_1") (pintype "passive"))
      (node (ref "C118") (pin "1") (pinfunction "1_1") (pintype "passive"))
      (node (ref "D33") (pin "2") (pinfunction "A_2") (pintype "passive"))
      (node (ref "D34") (pin "2") (pinfunction "A_2") (pintype "passive"))
      (node (ref "IC13") (pin "12") (pinfunction "GND_12") (pintype "power_in"))
      (node (ref "IC13") (pin "21") (pinfunction "EP_21") (pintype "power_in"))
      (node (ref "IC72") (pin "12") (pinfunction "GND_12") (pintype "power_in"))
      (node (ref "IC72") (pin "21") (pinfunction "EP_21") (pintype "power_in"))
      (node (ref "IC79") (pin "1") (pinfunction "PGND_1") (pintype "power_in"))
      (node (ref "IC79") (pin "11") (pinfunction "EP_11") (pintype "power_in"))
      (node (ref "IC79") (pin "6") (pinfunction "AGND_6") (pintype "power_in"))
      (node (ref "LD22") (pin "1") (pinfunction "C_1") (pintype "passive"))
      (node (ref "LD23") (pin "1") (pinfunction "C_1") (pintype "passive"))
      (node (ref "LD27") (pin "1") (pinfunction "C_1") (pintype "passive"))
      (node (ref "LD28") (pin "1") (pinfunction "C_1") (pintype "passive"))
      (node (ref "MOD1") (pin "1") (pinfunction "GND_1") (pintype "power_in"))
      (node (ref "MOD1") (pin "14") (pinfunction "GND_14") (pintype "power_in"))
      (node (ref "MOD1") (pin "16") (pinfunction "GND_16") (pintype "power_in"))
      (node (ref "MOD1") (pin "19") (pinfunction "GND_19") (pintype "power_in"))
      (node (ref "MOD1") (pin "20") (pinfunction "GND_20") (pintype "power_in"))
      (node (ref "MOD1") (pin "21") (pinfunction "GND_21") (pintype "power_in"))
      (node (ref "MOD1") (pin "4") (pinfunction "GND_4") (pintype "power_in"))
      (node (ref "MOD1") (pin "9") (pinfunction "GND_9") (pintype "power_in"))
      (node (ref "R421") (pin "1") (pinfunction "1_1") (pintype "passive"))
      (node (ref "R80") (pin "1") (pinfunction "1_1") (pintype "passive"))
      (node (ref "R81") (pin "1") (pinfunction "1_1") (pintype "passive"))
      (node (ref "R83") (pin "1") (pinfunction "1_1") (pintype "passive"))
      (node (ref "R84") (pin "1") (pinfunction "1_1") (pintype "passive"))
      (node (ref "R85") (pin "1") (pinfunction "1_1") (pintype "passive"))
      (node (ref "T20") (pin "1") (pinfunction "E_1") (pintype "passive"))
      (node (ref "T20") (pin "4") (pinfunction "E_4") (pintype "passive"))
      (node (ref "T22") (pin "2") (pinfunction "S_2") (pintype "passive"))
      (node (ref "W2") (pin "4") (pinfunction "4_4") (pintype "bidirectional"))
    )
    (net (code "28") (name "MGTAVCC") (class "Default")
      (node (ref "L64") (pin "2") (pinfunction "2_2") (pintype "passive"))
      (node (ref "L65") (pin "2") (pinfunction "2_2") (pintype "passive"))
    )
    (net (code "29") (name "MGTAVTT") (class "Default")
      (node (ref "L34") (pin "2") (pinfunction "2_2") (pintype "passive"))
    )
    (net (code "30") (name "MGTVCCAUX") (class "Default")
      (node (ref "L69") (pin "1") (pinfunction "1_1") (pintype "passive"))
    )
    (net (code "31") (name "Net-(D32-A)") (class "Default")
      (node (ref "D32") (pin "2") (pinfunction "A_2") (pintype "passive"))
      (node (ref "MOD1") (pin "12") (pinfunction "EN_12") (pintype "input"))
      (node (ref "R86") (pin "1") (pinfunction "1_1") (pintype "passive"))
      (node (ref "W2") (pin "1") (pinfunction "1_1") (pintype "bidirectional"))
    )
    (net (code "32") (name "Net-(IC13-FB)") (class "Default")
      (node (ref "IC13") (pin "16") (pinfunction "FB_16") (pintype "output"))
      (node (ref "R79") (pin "1") (pinfunction "1_1") (pintype "passive"))
      (node (ref "R80") (pin "2") (pinfunction "2_2") (pintype "passive"))
    )
    (net (code "33") (name "Net-(IC13-SS)") (class "Default")
      (node (ref "C106") (pin "1") (pinfunction "1_1") (pintype "passive"))
      (node (ref "IC13") (pin "15") (pinfunction "SS_15") (pintype "passive"))
    )
    (net (code "34") (name "Net-(IC72-FB)") (class "Default")
      (node (ref "IC72") (pin "16") (pinfunction "FB_16") (pintype "output"))
      (node (ref "R82") (pin "1") (pinfunction "1_1") (pintype "passive"))
      (node (ref "R83") (pin "2") (pinfunction "2_2") (pintype "passive"))
    )
    (net (code "35") (name "Net-(IC72-SS)") (class "Default")
      (node (ref "C109") (pin "1") (pinfunction "1_1") (pintype "passive"))
      (node (ref "IC72") (pin "15") (pinfunction "SS_15") (pintype "passive"))
    )
    (net (code "36") (name "Net-(IC79-EN)") (class "Default")
      (node (ref "IC79") (pin "3") (pinfunction "EN_3") (pintype "input"))
      (node (ref "R88") (pin "1") (pinfunction "1_1") (pintype "passive"))
    )
    (net (code "37") (name "Net-(IC79-FB)") (class "Default")
      (node (ref "IC79") (pin "5") (pinfunction "FB_5") (pintype "input"))
      (node (ref "R418") (pin "1") (pinfunction "1_1") (pintype "passive"))
      (node (ref "R421") (pin "2") (pinfunction "2_2") (pintype "passive"))
    )
    (net (code "38") (name "Net-(LD22-A)") (class "Default")
      (node (ref "LD22") (pin "2") (pinfunction "A_2") (pintype "passive"))
      (node (ref "R89") (pin "1") (pinfunction "1_1") (pintype "passive"))
    )
    (net (code "39") (name "Net-(LD23-A)") (class "Default")
      (node (ref "LD23") (pin "2") (pinfunction "A_2") (pintype "passive"))
      (node (ref "R90") (pin "1") (pinfunction "1_1") (pintype "passive"))
    )
    (net (code "40") (name "Net-(LD24-A)") (class "Default")
      (node (ref "LD24") (pin "2") (pinfunction "A_2") (pintype "passive"))
      (node (ref "R91") (pin "1") (pinfunction "1_1") (pintype "passive"))
    )
    (net (code "41") (name "Net-(LD24-C)") (class "Default")
      (node (ref "LD24") (pin "1") (pinfunction "C_1") (pintype "passive"))
      (node (ref "T20") (pin "6") (pinfunction "C_6") (pintype "passive"))
    )
    (net (code "42") (name "Net-(LD25-A)") (class "Default")
      (node (ref "LD25") (pin "2") (pinfunction "A_2") (pintype "passive"))
      (node (ref "R92") (pin "1") (pinfunction "1_1") (pintype "passive"))
    )
    (net (code "43") (name "Net-(LD25-C)") (class "Default")
      (node (ref "LD25") (pin "1") (pinfunction "C_1") (pintype "passive"))
      (node (ref "T20") (pin "3") (pinfunction "C_3") (pintype "passive"))
    )
    (net (code "44") (name "Net-(LD26-A)") (class "Default")
      (node (ref "LD26") (pin "2") (pinfunction "A_2") (pintype "passive"))
      (node (ref "R93") (pin "1") (pinfunction "1_1") (pintype "passive"))
    )
    (net (code "45") (name "Net-(LD26-C)") (class "Default")
      (node (ref "LD26") (pin "1") (pinfunction "C_1") (pintype "passive"))
      (node (ref "T22") (pin "3") (pinfunction "D_3") (pintype "passive"))
    )
    (net (code "46") (name "Net-(LD27-A)") (class "Default")
      (node (ref "LD27") (pin "2") (pinfunction "A_2") (pintype "passive"))
      (node (ref "R94") (pin "1") (pinfunction "1_1") (pintype "passive"))
    )
    (net (code "47") (name "Net-(LD28-A)") (class "Default")
      (node (ref "LD28") (pin "2") (pinfunction "A_2") (pintype "passive"))
      (node (ref "R95") (pin "1") (pinfunction "1_1") (pintype "passive"))
    )
    (net (code "48") (name "Net-(T20A-B)") (class "Default")
      (node (ref "R419") (pin "2") (pinfunction "2_2") (pintype "passive"))
      (node (ref "T20") (pin "2") (pinfunction "B_2") (pintype "passive"))
    )
    (net (code "49") (name "Net-(T20B-B)") (class "Default")
      (node (ref "R420") (pin "2") (pinfunction "2_2") (pintype "passive"))
      (node (ref "T20") (pin "5") (pinfunction "B_5") (pintype "passive"))
    )
    (net (code "50") (name "P0V95") (class "Default")
      (node (ref "R419") (pin "1") (pinfunction "1_1") (pintype "passive"))
      (node (ref "TP44") (pin "1") (pinfunction "1_1") (pintype "bidirectional"))
    )
    (net (code "51") (name "P0V95B") (class "Default")
      (node (ref "C107") (pin "2") (pinfunction "2_2") (pintype "passive"))
      (node (ref "IC72") (pin "1") (pinfunction "OUT_1") (pintype "power_in"))
      (node (ref "IC72") (pin "18") (pinfunction "OUT_18") (pintype "power_in"))
      (node (ref "IC72") (pin "19") (pinfunction "OUT_19") (pintype "power_in"))
      (node (ref "IC72") (pin "20") (pinfunction "OUT_20") (pintype "power_in"))
      (node (ref "L48") (pin "1") (pinfunction "1_1") (pintype "passive"))
      (node (ref "R82") (pin "2") (pinfunction "2_2") (pintype "passive"))
    )
    (net (code "52") (name "P1V0") (class "Default")
      (node (ref "C104") (pin "2") (pinfunction "2_2") (pintype "passive"))
      (node (ref "IC72") (pin "5") (pinfunction "IN_5") (pintype "input"))
      (node (ref "IC72") (pin "6") (pinfunction "IN_6") (pintype "input"))
      (node (ref "IC72") (pin "7") (pinfunction "IN_7") (pintype "input"))
      (node (ref "IC72") (pin "8") (pinfunction "IN_8") (pintype "input"))
      (node (ref "L62") (pin "1") (pinfunction "1_1") (pintype "passive"))
    )
    (net (code "53") (name "P1V2") (class "Default")
      (node (ref "C103") (pin "2") (pinfunction "2_2") (pintype "passive"))
      (node (ref "IC13") (pin "1") (pinfunction "OUT_1") (pintype "power_in"))
      (node (ref "IC13") (pin "18") (pinfunction "OUT_18") (pintype "power_in"))
      (node (ref "IC13") (pin "19") (pinfunction "OUT_19") (pintype "power_in"))
      (node (ref "IC13") (pin "20") (pinfunction "OUT_20") (pintype "power_in"))
      (node (ref "L34") (pin "1") (pinfunction "1_1") (pintype "passive"))
      (node (ref "R79") (pin "2") (pinfunction "2_2") (pintype "passive"))
      (node (ref "TP48") (pin "1") (pinfunction "1_1") (pintype "bidirectional"))
    )
    (net (code "54") (name "P1V5") (class "Default")
      (node (ref "L35") (pin "2") (pinfunction "2_2") (pintype "passive"))
      (node (ref "L70") (pin "2") (pinfunction "2_2") (pintype "passive"))
      (node (ref "L71") (pin "2") (pinfunction "2_2") (pintype "passive"))
      (node (ref "R420") (pin "1") (pinfunction "1_1") (pintype "passive"))
      (node (ref "TP45") (pin "1") (pinfunction "1_1") (pintype "bidirectional"))
    )
    (net (code "55") (name "P1V8") (class "Default")
      (node (ref "L66") (pin "2") (pinfunction "2_2") (pintype "passive"))
      (node (ref "L67") (pin "1") (pinfunction "1_1") (pintype "passive"))
      (node (ref "L68") (pin "2") (pinfunction "2_2") (pintype "passive"))
      (node (ref "L69") (pin "2") (pinfunction "2_2") (pintype "passive"))
      (node (ref "T22") (pin "1") (pinfunction "G_1") (pintype "passive"))
      (node (ref "TP46") (pin "1") (pinfunction "1_1") (pintype "bidirectional"))
    )
    (net (code "56") (name "P3V3") (class "Default")
      (node (ref "L49") (pin "2") (pinfunction "2_2") (pintype "passive"))
      (node (ref "L61") (pin "2") (pinfunction "2_2") (pintype "passive"))
      (node (ref "R95") (pin "2") (pinfunction "2_2") (pintype "passive"))
      (node (ref "TP47") (pin "1") (pinfunction "1_1") (pintype "bidirectional"))
    )
    (net (code "57") (name "P3V3MP") (class "Default")
      (node (ref "D32") (pin "1") (pinfunction "C_1") (pintype "passive"))
      (node (ref "MOD1") (pin "5") (pinfunction "P3V3_IN_5") (pintype "power_in"))
      (node (ref "R77") (pin "2") (pinfunction "2_2") (pintype "passive"))
      (node (ref "R78") (pin "2") (pinfunction "2_2") (pintype "passive"))
      (node (ref "R87") (pin "1") (pinfunction "1_1") (pintype "passive"))
      (node (ref "R89") (pin "2") (pinfunction "2_2") (pintype "passive"))
    )
    (net (code "58") (name "P5V0") (class "Default")
      (node (ref "C105") (pin "2") (pinfunction "2_2") (pintype "passive"))
      (node (ref "C108") (pin "2") (pinfunction "2_2") (pintype "passive"))
      (node (ref "IC13") (pin "10") (pinfunction "BIAS_10") (pintype "input"))
      (node (ref "IC72") (pin "10") (pinfunction "BIAS_10") (pintype "input"))
      (node (ref "R90") (pin "2") (pinfunction "2_2") (pintype "passive"))
      (node (ref "TP43") (pin "1") (pinfunction "1_1") (pintype "bidirectional"))
    )
    (net (code "59") (name "P6V0") (class "Default")
      (node (ref "C117") (pin "2") (pinfunction "2_2") (pintype "passive"))
      (node (ref "L73") (pin "2") (pinfunction "2_2") (pintype "passive"))
    )
    (net (code "60") (name "P12V0") (class "Default")
      (node (ref "C115") (pin "2") (pinfunction "2_2") (pintype "passive"))
      (node (ref "C118") (pin "2") (pinfunction "2_2") (pintype "passive"))
      (node (ref "IC79") (pin "2") (pinfunction "VIN_2") (pintype "input"))
      (node (ref "MOD1") (pin "15") (pinfunction "VIN_15") (pintype "input"))
      (node (ref "R91") (pin "2") (pinfunction "2_2") (pintype "passive"))
      (node (ref "R92") (pin "2") (pinfunction "2_2") (pintype "passive"))
      (node (ref "R93") (pin "2") (pinfunction "2_2") (pintype "passive"))
      (node (ref "R94") (pin "2") (pinfunction "2_2") (pintype "passive"))
    )
    (net (code "61") (name "VCCAUX") (class "Default")
      (node (ref "L67") (pin "2") (pinfunction "2_2") (pintype "passive"))
    )
    (net (code "62") (name "VCCBRAM") (class "Default")
      (node (ref "L48") (pin "2") (pinfunction "2_2") (pintype "passive"))
      (node (ref "R76") (pin "2") (pinfunction "2_2") (pintype "passive"))
    )
    (net (code "63") (name "VCCINT") (class "Default")
      (node (ref "R76") (pin "1") (pinfunction "1_1") (pintype "passive"))
      (node (ref "TP49") (pin "1") (pinfunction "1_1") (pintype "bidirectional"))
    )
    (net (code "64") (name "unconnected-(IC13-NC-Pad2)") (class "Default")
      (node (ref "IC13") (pin "2") (pinfunction "NC_2") (pintype "passive"))
    )
    (net (code "65") (name "unconnected-(IC13-NC-Pad3)") (class "Default")
      (node (ref "IC13") (pin "3") (pinfunction "NC_3") (pintype "passive"))
    )
    (net (code "66") (name "unconnected-(IC13-NC-Pad4)") (class "Default")
      (node (ref "IC13") (pin "4") (pinfunction "NC_4") (pintype "passive"))
    )
    (net (code "67") (name "unconnected-(IC13-NC-Pad13)") (class "Default")
      (node (ref "IC13") (pin "13") (pinfunction "NC_13") (pintype "passive"))
    )
    (net (code "68") (name "unconnected-(IC13-NC-Pad14)") (class "Default")
      (node (ref "IC13") (pin "14") (pinfunction "NC_14") (pintype "passive"))
    )
    (net (code "69") (name "unconnected-(IC13-NC-Pad17)") (class "Default")
      (node (ref "IC13") (pin "17") (pinfunction "NC_17") (pintype "passive"))
    )
    (net (code "70") (name "unconnected-(IC72-NC-Pad2)") (class "Default")
      (node (ref "IC72") (pin "2") (pinfunction "NC_2") (pintype "passive"))
    )
    (net (code "71") (name "unconnected-(IC72-NC-Pad3)") (class "Default")
      (node (ref "IC72") (pin "3") (pinfunction "NC_3") (pintype "passive"))
    )
    (net (code "72") (name "unconnected-(IC72-NC-Pad4)") (class "Default")
      (node (ref "IC72") (pin "4") (pinfunction "NC_4") (pintype "passive"))
    )
    (net (code "73") (name "unconnected-(IC72-NC-Pad13)") (class "Default")
      (node (ref "IC72") (pin "13") (pinfunction "NC_13") (pintype "passive"))
    )
    (net (code "74") (name "unconnected-(IC72-NC-Pad14)") (class "Default")
      (node (ref "IC72") (pin "14") (pinfunction "NC_14") (pintype "passive"))
    )
    (net (code "75") (name "unconnected-(IC72-NC-Pad17)") (class "Default")
      (node (ref "IC72") (pin "17") (pinfunction "NC_17") (pintype "passive"))
    )
    (net (code "76") (name "unconnected-(IC79-NC-Pad4)") (class "Default")
      (node (ref "IC79") (pin "4") (pinfunction "NC_4") (pintype "passive+no_connect"))
    )
  )
)
